# Main.net
KiCad netlist of a schematic drawn in Altium Designer
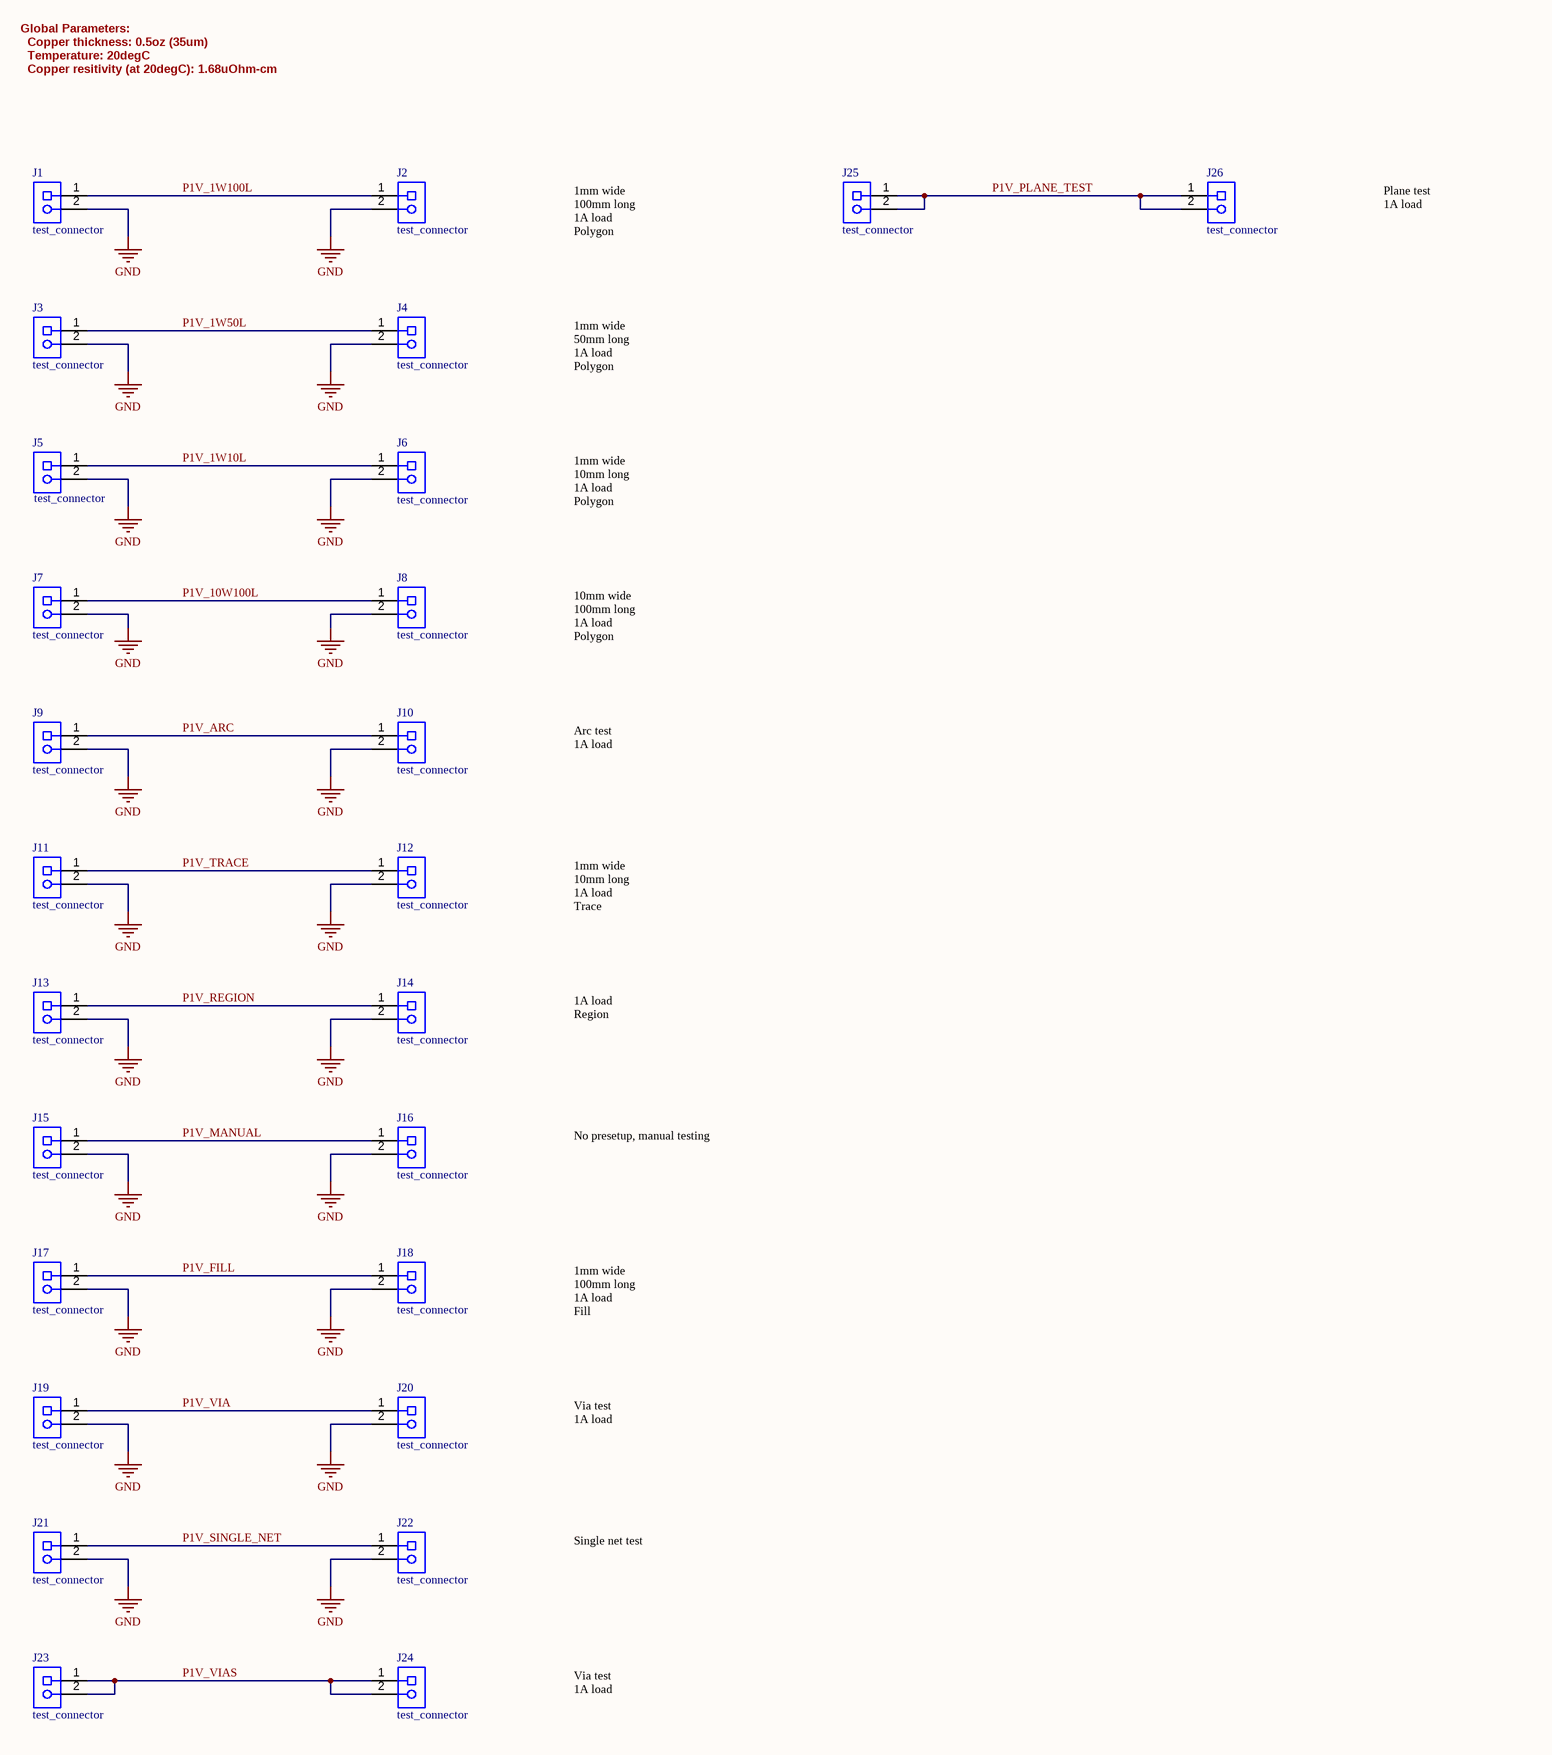
[diagram p0: Main.SchDoc]

(export (version "E")
  (design (tool "Eeschema 10.0.6"))
  (components
    (comp (ref "J1")
      (value "test_connector")
      (footprint "test_connector_footprint")
      (description "for playing around with")
      (fields
        (field (name "MANUFACTURER") "Phoenix Contact")
        (field (name "MANUFACTURER PART NUMBER") "1729128")
      )
      (libsource (lib "") (part "test_conn_1"))
    )
    (comp (ref "J2")
      (value "test_connector")
      (footprint "test_connector_footprint")
      (description "for playing around with")
      (fields
        (field (name "MANUFACTURER") "Phoenix Contact")
        (field (name "MANUFACTURER PART NUMBER") "1729128")
      )
      (libsource (lib "Sandbox") (part "test_conn"))
    )
    (comp (ref "J3")
      (value "test_connector")
      (footprint "test_connector_footprint")
      (description "for playing around with")
      (fields
        (field (name "MANUFACTURER") "Phoenix Contact")
        (field (name "MANUFACTURER PART NUMBER") "1729128")
      )
      (libsource (lib "") (part "test_conn_1"))
    )
    (comp (ref "J4")
      (value "test_connector")
      (footprint "test_connector_footprint")
      (description "for playing around with")
      (fields
        (field (name "MANUFACTURER") "Phoenix Contact")
        (field (name "MANUFACTURER PART NUMBER") "1729128")
      )
      (libsource (lib "Sandbox") (part "test_conn"))
    )
    (comp (ref "J5")
      (value "test_connector")
      (footprint "test_connector_footprint")
      (description "for playing around with")
      (fields
        (field (name "MANUFACTURER") "Phoenix Contact")
        (field (name "MANUFACTURER PART NUMBER") "1729128")
      )
      (libsource (lib "") (part "test_conn_1"))
    )
    (comp (ref "J6")
      (value "test_connector")
      (footprint "test_connector_footprint")
      (description "for playing around with")
      (fields
        (field (name "MANUFACTURER") "Phoenix Contact")
        (field (name "MANUFACTURER PART NUMBER") "1729128")
      )
      (libsource (lib "Sandbox") (part "test_conn"))
    )
    (comp (ref "J7")
      (value "test_connector")
      (footprint "test_connector_footprint")
      (description "for playing around with")
      (fields
        (field (name "MANUFACTURER") "Phoenix Contact")
        (field (name "MANUFACTURER PART NUMBER") "1729128")
      )
      (libsource (lib "") (part "test_conn_1"))
    )
    (comp (ref "J8")
      (value "test_connector")
      (footprint "test_connector_footprint")
      (description "for playing around with")
      (fields
        (field (name "MANUFACTURER") "Phoenix Contact")
        (field (name "MANUFACTURER PART NUMBER") "1729128")
      )
      (libsource (lib "Sandbox") (part "test_conn"))
    )
    (comp (ref "J9")
      (value "test_connector")
      (footprint "test_connector_footprint")
      (description "for playing around with")
      (fields
        (field (name "MANUFACTURER") "Phoenix Contact")
        (field (name "MANUFACTURER PART NUMBER") "1729128")
      )
      (libsource (lib "") (part "test_conn_1"))
    )
    (comp (ref "J10")
      (value "test_connector")
      (footprint "test_connector_footprint")
      (description "for playing around with")
      (fields
        (field (name "MANUFACTURER") "Phoenix Contact")
        (field (name "MANUFACTURER PART NUMBER") "1729128")
      )
      (libsource (lib "Sandbox") (part "test_conn"))
    )
    (comp (ref "J11")
      (value "test_connector")
      (footprint "test_connector_footprint")
      (description "for playing around with")
      (fields
        (field (name "MANUFACTURER") "Phoenix Contact")
        (field (name "MANUFACTURER PART NUMBER") "1729128")
      )
      (libsource (lib "") (part "test_conn_1"))
    )
    (comp (ref "J12")
      (value "test_connector")
      (footprint "test_connector_footprint")
      (description "for playing around with")
      (fields
        (field (name "MANUFACTURER") "Phoenix Contact")
        (field (name "MANUFACTURER PART NUMBER") "1729128")
      )
      (libsource (lib "Sandbox") (part "test_conn"))
    )
    (comp (ref "J13")
      (value "test_connector")
      (footprint "test_connector_footprint")
      (description "for playing around with")
      (fields
        (field (name "MANUFACTURER") "Phoenix Contact")
        (field (name "MANUFACTURER PART NUMBER") "1729128")
      )
      (libsource (lib "") (part "test_conn_1"))
    )
    (comp (ref "J14")
      (value "test_connector")
      (footprint "test_connector_footprint")
      (description "for playing around with")
      (fields
        (field (name "MANUFACTURER") "Phoenix Contact")
        (field (name "MANUFACTURER PART NUMBER") "1729128")
      )
      (libsource (lib "Sandbox") (part "test_conn"))
    )
    (comp (ref "J15")
      (value "test_connector")
      (footprint "test_connector_footprint")
      (description "for playing around with")
      (fields
        (field (name "MANUFACTURER") "Phoenix Contact")
        (field (name "MANUFACTURER PART NUMBER") "1729128")
      )
      (libsource (lib "") (part "test_conn_1"))
    )
    (comp (ref "J16")
      (value "test_connector")
      (footprint "test_connector_footprint")
      (description "for playing around with")
      (fields
        (field (name "MANUFACTURER") "Phoenix Contact")
        (field (name "MANUFACTURER PART NUMBER") "1729128")
      )
      (libsource (lib "Sandbox") (part "test_conn"))
    )
    (comp (ref "J17")
      (value "test_connector")
      (footprint "test_connector_footprint")
      (description "for playing around with")
      (fields
        (field (name "MANUFACTURER") "Phoenix Contact")
        (field (name "MANUFACTURER PART NUMBER") "1729128")
      )
      (libsource (lib "") (part "test_conn_1"))
    )
    (comp (ref "J18")
      (value "test_connector")
      (footprint "test_connector_footprint")
      (description "for playing around with")
      (fields
        (field (name "MANUFACTURER") "Phoenix Contact")
        (field (name "MANUFACTURER PART NUMBER") "1729128")
      )
      (libsource (lib "Sandbox") (part "test_conn"))
    )
    (comp (ref "J19")
      (value "test_connector")
      (footprint "test_connector_footprint")
      (description "for playing around with")
      (fields
        (field (name "MANUFACTURER") "Phoenix Contact")
        (field (name "MANUFACTURER PART NUMBER") "1729128")
      )
      (libsource (lib "") (part "test_conn_1"))
    )
    (comp (ref "J20")
      (value "test_connector")
      (footprint "test_connector_footprint")
      (description "for playing around with")
      (fields
        (field (name "MANUFACTURER") "Phoenix Contact")
        (field (name "MANUFACTURER PART NUMBER") "1729128")
      )
      (libsource (lib "Sandbox") (part "test_conn"))
    )
    (comp (ref "J21")
      (value "test_connector")
      (footprint "test_connector_footprint")
      (description "for playing around with")
      (fields
        (field (name "MANUFACTURER") "Phoenix Contact")
        (field (name "MANUFACTURER PART NUMBER") "1729128")
      )
      (libsource (lib "") (part "test_conn_1"))
    )
    (comp (ref "J22")
      (value "test_connector")
      (footprint "test_connector_footprint")
      (description "for playing around with")
      (fields
        (field (name "MANUFACTURER") "Phoenix Contact")
        (field (name "MANUFACTURER PART NUMBER") "1729128")
      )
      (libsource (lib "Sandbox") (part "test_conn"))
    )
    (comp (ref "J23")
      (value "test_connector")
      (footprint "test_connector_footprint")
      (description "for playing around with")
      (fields
        (field (name "MANUFACTURER") "Phoenix Contact")
        (field (name "MANUFACTURER PART NUMBER") "1729128")
      )
      (libsource (lib "") (part "test_conn_1"))
    )
    (comp (ref "J24")
      (value "test_connector")
      (footprint "test_connector_footprint")
      (description "for playing around with")
      (fields
        (field (name "MANUFACTURER") "Phoenix Contact")
        (field (name "MANUFACTURER PART NUMBER") "1729128")
      )
      (libsource (lib "Sandbox") (part "test_conn"))
    )
    (comp (ref "J25")
      (value "test_connector")
      (footprint "test_connector_footprint")
      (description "for playing around with")
      (fields
        (field (name "MANUFACTURER") "Phoenix Contact")
        (field (name "MANUFACTURER PART NUMBER") "1729128")
      )
      (libsource (lib "") (part "test_conn_1"))
    )
    (comp (ref "J26")
      (value "test_connector")
      (footprint "test_connector_footprint")
      (description "for playing around with")
      (fields
        (field (name "MANUFACTURER") "Phoenix Contact")
        (field (name "MANUFACTURER PART NUMBER") "1729128")
      )
      (libsource (lib "Sandbox") (part "test_conn"))
    )
  )
  (nets
    (net (code "1") (name "/P1V_1W10L") (class "Default")
      (node (ref "J5") (pin "1") (pinfunction "1_1") (pintype "passive"))
      (node (ref "J6") (pin "1") (pinfunction "1_1") (pintype "passive"))
    )
    (net (code "2") (name "/P1V_1W50L") (class "Default")
      (node (ref "J3") (pin "1") (pinfunction "1_1") (pintype "passive"))
      (node (ref "J4") (pin "1") (pinfunction "1_1") (pintype "passive"))
    )
    (net (code "3") (name "/P1V_1W100L") (class "Default")
      (node (ref "J1") (pin "1") (pinfunction "1_1") (pintype "passive"))
      (node (ref "J2") (pin "1") (pinfunction "1_1") (pintype "passive"))
    )
    (net (code "4") (name "/P1V_10W100L") (class "Default")
      (node (ref "J7") (pin "1") (pinfunction "1_1") (pintype "passive"))
      (node (ref "J8") (pin "1") (pinfunction "1_1") (pintype "passive"))
    )
    (net (code "5") (name "/P1V_ARC") (class "Default")
      (node (ref "J10") (pin "1") (pinfunction "1_1") (pintype "passive"))
      (node (ref "J9") (pin "1") (pinfunction "1_1") (pintype "passive"))
    )
    (net (code "6") (name "/P1V_FILL") (class "Default")
      (node (ref "J17") (pin "1") (pinfunction "1_1") (pintype "passive"))
      (node (ref "J18") (pin "1") (pinfunction "1_1") (pintype "passive"))
    )
    (net (code "7") (name "/P1V_MANUAL") (class "Default")
      (node (ref "J15") (pin "1") (pinfunction "1_1") (pintype "passive"))
      (node (ref "J16") (pin "1") (pinfunction "1_1") (pintype "passive"))
    )
    (net (code "8") (name "/P1V_PLANE_TEST") (class "Default")
      (node (ref "J25") (pin "1") (pinfunction "1_1") (pintype "passive"))
      (node (ref "J25") (pin "2") (pinfunction "2_2") (pintype "passive"))
      (node (ref "J26") (pin "1") (pinfunction "1_1") (pintype "passive"))
      (node (ref "J26") (pin "2") (pinfunction "2_2") (pintype "passive"))
    )
    (net (code "9") (name "/P1V_REGION") (class "Default")
      (node (ref "J13") (pin "1") (pinfunction "1_1") (pintype "passive"))
      (node (ref "J14") (pin "1") (pinfunction "1_1") (pintype "passive"))
    )
    (net (code "10") (name "/P1V_SINGLE_NET") (class "Default")
      (node (ref "J21") (pin "1") (pinfunction "1_1") (pintype "passive"))
      (node (ref "J22") (pin "1") (pinfunction "1_1") (pintype "passive"))
    )
    (net (code "11") (name "/P1V_TRACE") (class "Default")
      (node (ref "J11") (pin "1") (pinfunction "1_1") (pintype "passive"))
      (node (ref "J12") (pin "1") (pinfunction "1_1") (pintype "passive"))
    )
    (net (code "12") (name "/P1V_VIA") (class "Default")
      (node (ref "J19") (pin "1") (pinfunction "1_1") (pintype "passive"))
      (node (ref "J20") (pin "1") (pinfunction "1_1") (pintype "passive"))
    )
    (net (code "13") (name "/P1V_VIAS") (class "Default")
      (node (ref "J23") (pin "1") (pinfunction "1_1") (pintype "passive"))
      (node (ref "J23") (pin "2") (pinfunction "2_2") (pintype "passive"))
      (node (ref "J24") (pin "1") (pinfunction "1_1") (pintype "passive"))
      (node (ref "J24") (pin "2") (pinfunction "2_2") (pintype "passive"))
    )
    (net (code "14") (name "GND") (class "Default")
      (node (ref "J1") (pin "2") (pinfunction "2_2") (pintype "passive"))
      (node (ref "J10") (pin "2") (pinfunction "2_2") (pintype "passive"))
      (node (ref "J11") (pin "2") (pinfunction "2_2") (pintype "passive"))
      (node (ref "J12") (pin "2") (pinfunction "2_2") (pintype "passive"))
      (node (ref "J13") (pin "2") (pinfunction "2_2") (pintype "passive"))
      (node (ref "J14") (pin "2") (pinfunction "2_2") (pintype "passive"))
      (node (ref "J15") (pin "2") (pinfunction "2_2") (pintype "passive"))
      (node (ref "J16") (pin "2") (pinfunction "2_2") (pintype "passive"))
      (node (ref "J17") (pin "2") (pinfunction "2_2") (pintype "passive"))
      (node (ref "J18") (pin "2") (pinfunction "2_2") (pintype "passive"))
      (node (ref "J19") (pin "2") (pinfunction "2_2") (pintype "passive"))
      (node (ref "J2") (pin "2") (pinfunction "2_2") (pintype "passive"))
      (node (ref "J20") (pin "2") (pinfunction "2_2") (pintype "passive"))
      (node (ref "J21") (pin "2") (pinfunction "2_2") (pintype "passive"))
      (node (ref "J22") (pin "2") (pinfunction "2_2") (pintype "passive"))
      (node (ref "J3") (pin "2") (pinfunction "2_2") (pintype "passive"))
      (node (ref "J4") (pin "2") (pinfunction "2_2") (pintype "passive"))
      (node (ref "J5") (pin "2") (pinfunction "2_2") (pintype "passive"))
      (node (ref "J6") (pin "2") (pinfunction "2_2") (pintype "passive"))
      (node (ref "J7") (pin "2") (pinfunction "2_2") (pintype "passive"))
      (node (ref "J8") (pin "2") (pinfunction "2_2") (pintype "passive"))
      (node (ref "J9") (pin "2") (pinfunction "2_2") (pintype "passive"))
    )
  )
)
